# Switch-LIN-SIL-1.net
KiCad netlist of a schematic drawn in EAGLE
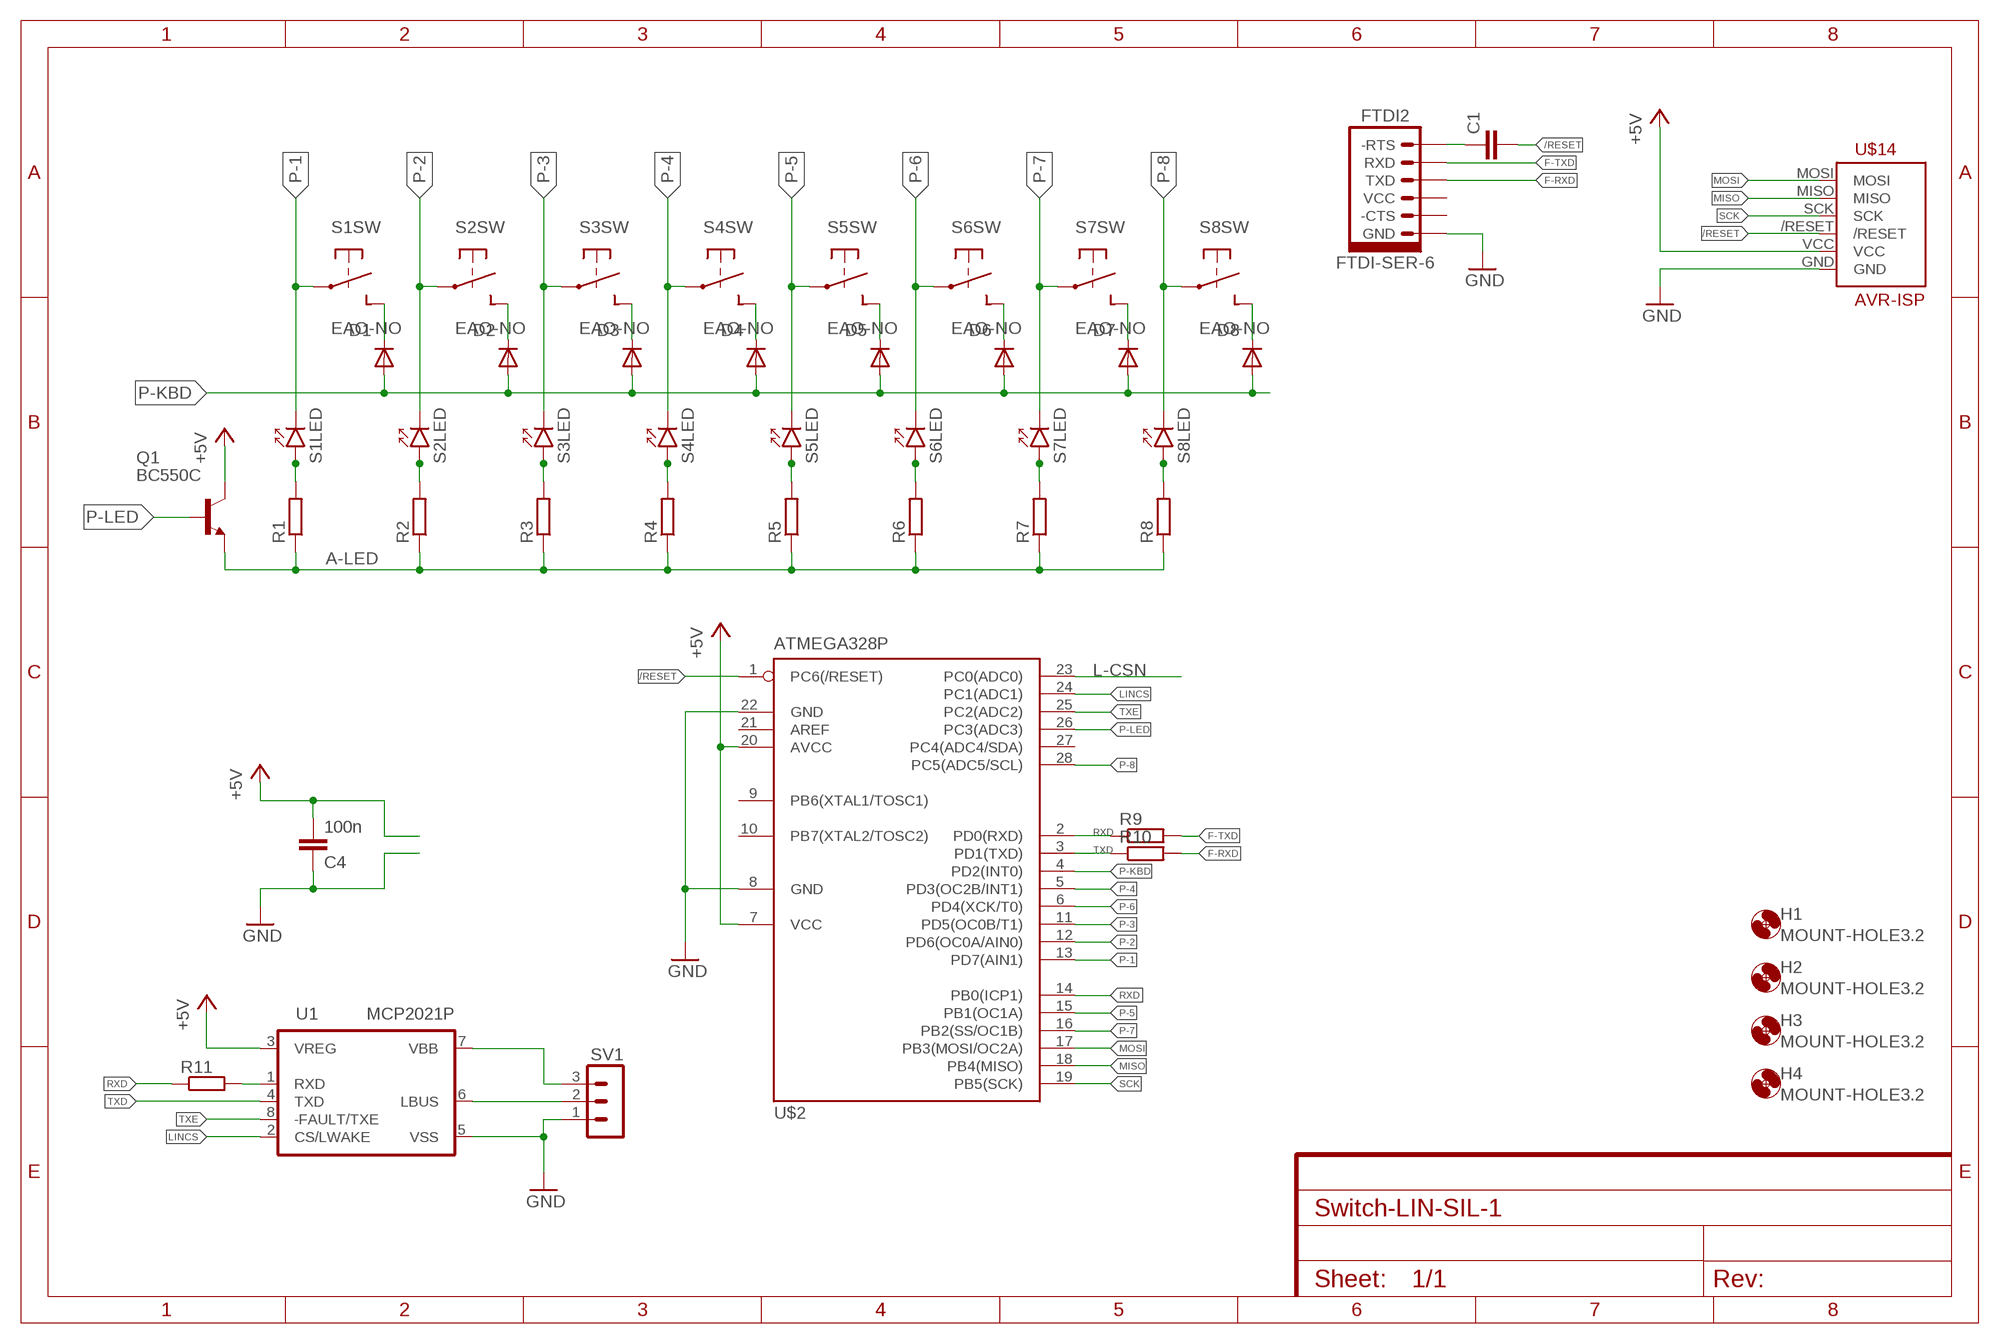
[diagram p0: schematic, sheet 1]

(export (version "E")
  (design (tool "Eeschema 10.0.6"))
  (components
    (comp (ref "C1")
      (value "C-EU025-025X050")
      (footprint "eagle-import:C025-025X050")
      (libsource (lib "eagle-import") (part "C-EU025-025X050"))
    )
    (comp (ref "C4")
      (value "100n")
      (footprint "eagle-import:C0805")
      (libsource (lib "eagle-import") (part "C-EUC0805"))
    )
    (comp (ref "D1")
      (value "1N4148")
      (footprint "eagle-import:DO35-7")
      (libsource (lib "eagle-import") (part "1N4148DO35-7"))
    )
    (comp (ref "D2")
      (value "1N4148")
      (footprint "eagle-import:DO35-7")
      (libsource (lib "eagle-import") (part "1N4148DO35-7"))
    )
    (comp (ref "D3")
      (value "1N4148")
      (footprint "eagle-import:DO35-7")
      (libsource (lib "eagle-import") (part "1N4148DO35-7"))
    )
    (comp (ref "D4")
      (value "1N4148")
      (footprint "eagle-import:DO35-7")
      (libsource (lib "eagle-import") (part "1N4148DO35-7"))
    )
    (comp (ref "D5")
      (value "1N4148")
      (footprint "eagle-import:DO35-7")
      (libsource (lib "eagle-import") (part "1N4148DO35-7"))
    )
    (comp (ref "D6")
      (value "1N4148")
      (footprint "eagle-import:DO35-7")
      (libsource (lib "eagle-import") (part "1N4148DO35-7"))
    )
    (comp (ref "D7")
      (value "1N4148")
      (footprint "eagle-import:DO35-7")
      (libsource (lib "eagle-import") (part "1N4148DO35-7"))
    )
    (comp (ref "D8")
      (value "1N4148")
      (footprint "eagle-import:DO35-7")
      (libsource (lib "eagle-import") (part "1N4148DO35-7"))
    )
    (comp (ref "FTDI2")
      (value "FTDI-SER-6")
      (footprint "eagle-import:FTDI-SER-6")
      (libsource (lib "eagle-import") (part "FTDI-SER-6"))
    )
    (comp (ref "H1")
      (value "MOUNT-HOLE3.2")
      (footprint "eagle-import:3,2")
      (libsource (lib "eagle-import") (part "MOUNT-HOLE3.2"))
    )
    (comp (ref "H2")
      (value "MOUNT-HOLE3.2")
      (footprint "eagle-import:3,2")
      (libsource (lib "eagle-import") (part "MOUNT-HOLE3.2"))
    )
    (comp (ref "H3")
      (value "MOUNT-HOLE3.2")
      (footprint "eagle-import:3,2")
      (libsource (lib "eagle-import") (part "MOUNT-HOLE3.2"))
    )
    (comp (ref "H4")
      (value "MOUNT-HOLE3.2")
      (footprint "eagle-import:3,2")
      (libsource (lib "eagle-import") (part "MOUNT-HOLE3.2"))
    )
    (comp (ref "Q1")
      (value "BC550C")
      (footprint "eagle-import:TO92-EBC")
      (libsource (lib "eagle-import") (part "BC550C"))
    )
    (comp (ref "R1")
      (value "R-EU_0207/7")
      (footprint "eagle-import:0207_7")
      (libsource (lib "eagle-import") (part "R-EU_0207/7"))
    )
    (comp (ref "R2")
      (value "R-EU_0207/7")
      (footprint "eagle-import:0207_7")
      (libsource (lib "eagle-import") (part "R-EU_0207/7"))
    )
    (comp (ref "R3")
      (value "R-EU_0207/7")
      (footprint "eagle-import:0207_7")
      (libsource (lib "eagle-import") (part "R-EU_0207/7"))
    )
    (comp (ref "R4")
      (value "R-EU_0207/7")
      (footprint "eagle-import:0207_7")
      (libsource (lib "eagle-import") (part "R-EU_0207/7"))
    )
    (comp (ref "R5")
      (value "R-EU_0207/7")
      (footprint "eagle-import:0207_7")
      (libsource (lib "eagle-import") (part "R-EU_0207/7"))
    )
    (comp (ref "R6")
      (value "R-EU_0207/7")
      (footprint "eagle-import:0207_7")
      (libsource (lib "eagle-import") (part "R-EU_0207/7"))
    )
    (comp (ref "R7")
      (value "R-EU_0207/7")
      (footprint "eagle-import:0207_7")
      (libsource (lib "eagle-import") (part "R-EU_0207/7"))
    )
    (comp (ref "R8")
      (value "R-EU_0207/7")
      (footprint "eagle-import:0207_7")
      (libsource (lib "eagle-import") (part "R-EU_0207/7"))
    )
    (comp (ref "R9")
      (value "R-EU_0207/7")
      (footprint "eagle-import:0207_7")
      (libsource (lib "eagle-import") (part "R-EU_0207/7"))
    )
    (comp (ref "R10")
      (value "R-EU_0207/7")
      (footprint "eagle-import:0207_7")
      (libsource (lib "eagle-import") (part "R-EU_0207/7"))
    )
    (comp (ref "R11")
      (value "R-EU_0207/7")
      (footprint "eagle-import:0207_7")
      (libsource (lib "eagle-import") (part "R-EU_0207/7"))
    )
    (comp (ref "S1")
      (value "EAO-NO")
      (footprint "eagle-import:MA04-1")
      (libsource (lib "eagle-import") (part "EAO-NO"))
    )
    (comp (ref "S2")
      (value "EAO-NO")
      (footprint "eagle-import:MA04-1")
      (libsource (lib "eagle-import") (part "EAO-NO"))
    )
    (comp (ref "S3")
      (value "EAO-NO")
      (footprint "eagle-import:MA04-1")
      (libsource (lib "eagle-import") (part "EAO-NO"))
    )
    (comp (ref "S4")
      (value "EAO-NO")
      (footprint "eagle-import:MA04-1")
      (libsource (lib "eagle-import") (part "EAO-NO"))
    )
    (comp (ref "S5")
      (value "EAO-NO")
      (footprint "eagle-import:MA04-1")
      (libsource (lib "eagle-import") (part "EAO-NO"))
    )
    (comp (ref "S6")
      (value "EAO-NO")
      (footprint "eagle-import:MA04-1")
      (libsource (lib "eagle-import") (part "EAO-NO"))
    )
    (comp (ref "S7")
      (value "EAO-NO")
      (footprint "eagle-import:MA04-1")
      (libsource (lib "eagle-import") (part "EAO-NO"))
    )
    (comp (ref "S8")
      (value "EAO-NO")
      (footprint "eagle-import:MA04-1")
      (libsource (lib "eagle-import") (part "EAO-NO"))
    )
    (comp (ref "SV1")
      (value "MA03-1")
      (footprint "eagle-import:MA03-1")
      (libsource (lib "eagle-import") (part "MA03-1"))
    )
    (comp (ref "U$2")
      (value "ATMEGA328P")
      (footprint "eagle-import:DIL28-3")
      (libsource (lib "eagle-import") (part "ATMEGA328P"))
    )
    (comp (ref "U$14")
      (value "AVR-ISP")
      (footprint "eagle-import:AVR-ISP-SIL")
      (libsource (lib "eagle-import") (part "AVR-ISP"))
    )
    (comp (ref "U1")
      (value "MCP2021P")
      (footprint "eagle-import:DIL8")
      (libsource (lib "eagle-import") (part "MCP2021P"))
    )
  )
  (nets
    (net (code "1") (name "+5V") (class "Default")
      (node (ref "C4") (pin "2") (pinfunction "2_2") (pintype "passive"))
      (node (ref "Q1") (pin "C") (pinfunction "C_C") (pintype "passive"))
      (node (ref "U$14") (pin "VCC") (pinfunction "VCC_VCC") (pintype "bidirectional"))
      (node (ref "U$2") (pin "20") (pinfunction "AVCC_20") (pintype "power_in"))
      (node (ref "U$2") (pin "7") (pinfunction "VCC_7") (pintype "power_in"))
      (node (ref "U1") (pin "3") (pinfunction "VREG_3") (pintype "power_in"))
    )
    (net (code "2") (name "/A-LED") (class "Default")
      (node (ref "Q1") (pin "E") (pinfunction "E_E") (pintype "passive"))
      (node (ref "R1") (pin "1") (pinfunction "1_1") (pintype "passive"))
      (node (ref "R2") (pin "1") (pinfunction "1_1") (pintype "passive"))
      (node (ref "R3") (pin "1") (pinfunction "1_1") (pintype "passive"))
      (node (ref "R4") (pin "1") (pinfunction "1_1") (pintype "passive"))
      (node (ref "R5") (pin "1") (pinfunction "1_1") (pintype "passive"))
      (node (ref "R6") (pin "1") (pinfunction "1_1") (pintype "passive"))
      (node (ref "R7") (pin "1") (pinfunction "1_1") (pintype "passive"))
      (node (ref "R8") (pin "1") (pinfunction "1_1") (pintype "passive"))
    )
    (net (code "3") (name "/L-CSN") (class "Default")
      (node (ref "U$2") (pin "23") (pinfunction "PC0(ADC0)_23") (pintype "bidirectional"))
    )
    (net (code "4") (name "F-RXD") (class "Default")
      (node (ref "FTDI2") (pin "TXD") (pinfunction "TXD_TXD") (pintype "passive"))
      (node (ref "R10") (pin "2") (pinfunction "2_2") (pintype "passive"))
    )
    (net (code "5") (name "F-TXD") (class "Default")
      (node (ref "FTDI2") (pin "RXD") (pinfunction "RXD_RXD") (pintype "passive"))
      (node (ref "R9") (pin "2") (pinfunction "2_2") (pintype "passive"))
    )
    (net (code "6") (name "GND") (class "Default")
      (node (ref "C4") (pin "1") (pinfunction "1_1") (pintype "passive"))
      (node (ref "FTDI2") (pin "GND") (pinfunction "GND_GND") (pintype "passive"))
      (node (ref "SV1") (pin "1") (pinfunction "1_1") (pintype "passive"))
      (node (ref "U$14") (pin "GND") (pinfunction "GND_GND") (pintype "bidirectional"))
      (node (ref "U$2") (pin "22") (pinfunction "GND_22") (pintype "power_in"))
      (node (ref "U$2") (pin "8") (pinfunction "GND_8") (pintype "power_in"))
      (node (ref "U1") (pin "5") (pinfunction "VSS_5") (pintype "power_in"))
    )
    (net (code "7") (name "LINCS") (class "Default")
      (node (ref "U$2") (pin "24") (pinfunction "PC1(ADC1)_24") (pintype "bidirectional"))
      (node (ref "U1") (pin "2") (pinfunction "CS/LWAKE_2") (pintype "input"))
    )
    (net (code "8") (name "MISO") (class "Default")
      (node (ref "U$14") (pin "MISO") (pinfunction "MISO_MISO") (pintype "bidirectional"))
      (node (ref "U$2") (pin "18") (pinfunction "PB4(MISO)_18") (pintype "bidirectional"))
    )
    (net (code "9") (name "MOSI") (class "Default")
      (node (ref "U$14") (pin "MOSI") (pinfunction "MOSI_MOSI") (pintype "bidirectional"))
      (node (ref "U$2") (pin "17") (pinfunction "PB3(MOSI/OC2A)_17") (pintype "bidirectional"))
    )
    (net (code "10") (name "Net-(C1-Pad1)") (class "Default")
      (node (ref "C1") (pin "1") (pinfunction "1_1") (pintype "passive"))
      (node (ref "FTDI2") (pin "-RTS") (pinfunction "-RTS_-RTS") (pintype "passive"))
    )
    (net (code "11") (name "Net-(S1A-A)") (class "Default")
      (node (ref "R1") (pin "2") (pinfunction "2_2") (pintype "passive"))
      (node (ref "S1") (pin "2") (pinfunction "A_2") (pintype "passive"))
    )
    (net (code "12") (name "Net-(S1B-NO2)") (class "Default")
      (node (ref "D1") (pin "C") (pinfunction "C_C") (pintype "passive"))
      (node (ref "S1") (pin "4") (pinfunction "NO2_4") (pintype "passive"))
    )
    (net (code "13") (name "Net-(S2A-A)") (class "Default")
      (node (ref "R2") (pin "2") (pinfunction "2_2") (pintype "passive"))
      (node (ref "S2") (pin "2") (pinfunction "A_2") (pintype "passive"))
    )
    (net (code "14") (name "Net-(S2B-NO2)") (class "Default")
      (node (ref "D2") (pin "C") (pinfunction "C_C") (pintype "passive"))
      (node (ref "S2") (pin "4") (pinfunction "NO2_4") (pintype "passive"))
    )
    (net (code "15") (name "Net-(S3A-A)") (class "Default")
      (node (ref "R3") (pin "2") (pinfunction "2_2") (pintype "passive"))
      (node (ref "S3") (pin "2") (pinfunction "A_2") (pintype "passive"))
    )
    (net (code "16") (name "Net-(S3B-NO2)") (class "Default")
      (node (ref "D3") (pin "C") (pinfunction "C_C") (pintype "passive"))
      (node (ref "S3") (pin "4") (pinfunction "NO2_4") (pintype "passive"))
    )
    (net (code "17") (name "Net-(S4A-A)") (class "Default")
      (node (ref "R4") (pin "2") (pinfunction "2_2") (pintype "passive"))
      (node (ref "S4") (pin "2") (pinfunction "A_2") (pintype "passive"))
    )
    (net (code "18") (name "Net-(S4B-NO2)") (class "Default")
      (node (ref "D4") (pin "C") (pinfunction "C_C") (pintype "passive"))
      (node (ref "S4") (pin "4") (pinfunction "NO2_4") (pintype "passive"))
    )
    (net (code "19") (name "Net-(S5A-A)") (class "Default")
      (node (ref "R5") (pin "2") (pinfunction "2_2") (pintype "passive"))
      (node (ref "S5") (pin "2") (pinfunction "A_2") (pintype "passive"))
    )
    (net (code "20") (name "Net-(S5B-NO2)") (class "Default")
      (node (ref "D5") (pin "C") (pinfunction "C_C") (pintype "passive"))
      (node (ref "S5") (pin "4") (pinfunction "NO2_4") (pintype "passive"))
    )
    (net (code "21") (name "Net-(S6A-A)") (class "Default")
      (node (ref "R6") (pin "2") (pinfunction "2_2") (pintype "passive"))
      (node (ref "S6") (pin "2") (pinfunction "A_2") (pintype "passive"))
    )
    (net (code "22") (name "Net-(S6B-NO2)") (class "Default")
      (node (ref "D6") (pin "C") (pinfunction "C_C") (pintype "passive"))
      (node (ref "S6") (pin "4") (pinfunction "NO2_4") (pintype "passive"))
    )
    (net (code "23") (name "Net-(S7A-A)") (class "Default")
      (node (ref "R7") (pin "2") (pinfunction "2_2") (pintype "passive"))
      (node (ref "S7") (pin "2") (pinfunction "A_2") (pintype "passive"))
    )
    (net (code "24") (name "Net-(S7B-NO2)") (class "Default")
      (node (ref "D7") (pin "C") (pinfunction "C_C") (pintype "passive"))
      (node (ref "S7") (pin "4") (pinfunction "NO2_4") (pintype "passive"))
    )
    (net (code "25") (name "Net-(S8A-A)") (class "Default")
      (node (ref "R8") (pin "2") (pinfunction "2_2") (pintype "passive"))
      (node (ref "S8") (pin "2") (pinfunction "A_2") (pintype "passive"))
    )
    (net (code "26") (name "Net-(S8B-NO2)") (class "Default")
      (node (ref "D8") (pin "C") (pinfunction "C_C") (pintype "passive"))
      (node (ref "S8") (pin "4") (pinfunction "NO2_4") (pintype "passive"))
    )
    (net (code "27") (name "Net-(U1-LBUS)") (class "Default")
      (node (ref "SV1") (pin "2") (pinfunction "2_2") (pintype "passive"))
      (node (ref "U1") (pin "6") (pinfunction "LBUS_6") (pintype "bidirectional"))
    )
    (net (code "28") (name "Net-(U1-RXD)") (class "Default")
      (node (ref "R11") (pin "2") (pinfunction "2_2") (pintype "passive"))
      (node (ref "U1") (pin "1") (pinfunction "RXD_1") (pintype "output"))
    )
    (net (code "29") (name "Net-(U1-VBB)") (class "Default")
      (node (ref "SV1") (pin "3") (pinfunction "3_3") (pintype "passive"))
      (node (ref "U1") (pin "7") (pinfunction "VBB_7") (pintype "power_in"))
    )
    (net (code "30") (name "P-1") (class "Default")
      (node (ref "S1") (pin "1") (pinfunction "C_1") (pintype "passive"))
      (node (ref "S1") (pin "3") (pinfunction "NO1_3") (pintype "passive"))
      (node (ref "U$2") (pin "13") (pinfunction "PD7(AIN1)_13") (pintype "bidirectional"))
    )
    (net (code "31") (name "P-2") (class "Default")
      (node (ref "S2") (pin "1") (pinfunction "C_1") (pintype "passive"))
      (node (ref "S2") (pin "3") (pinfunction "NO1_3") (pintype "passive"))
      (node (ref "U$2") (pin "12") (pinfunction "PD6(OC0A/AIN0)_12") (pintype "bidirectional"))
    )
    (net (code "32") (name "P-3") (class "Default")
      (node (ref "S3") (pin "1") (pinfunction "C_1") (pintype "passive"))
      (node (ref "S3") (pin "3") (pinfunction "NO1_3") (pintype "passive"))
      (node (ref "U$2") (pin "11") (pinfunction "PD5(OC0B/T1)_11") (pintype "bidirectional"))
    )
    (net (code "33") (name "P-4") (class "Default")
      (node (ref "S4") (pin "1") (pinfunction "C_1") (pintype "passive"))
      (node (ref "S4") (pin "3") (pinfunction "NO1_3") (pintype "passive"))
      (node (ref "U$2") (pin "5") (pinfunction "PD3(OC2B/INT1)_5") (pintype "bidirectional"))
    )
    (net (code "34") (name "P-5") (class "Default")
      (node (ref "S5") (pin "1") (pinfunction "C_1") (pintype "passive"))
      (node (ref "S5") (pin "3") (pinfunction "NO1_3") (pintype "passive"))
      (node (ref "U$2") (pin "15") (pinfunction "PB1(OC1A)_15") (pintype "bidirectional"))
    )
    (net (code "35") (name "P-6") (class "Default")
      (node (ref "S6") (pin "1") (pinfunction "C_1") (pintype "passive"))
      (node (ref "S6") (pin "3") (pinfunction "NO1_3") (pintype "passive"))
      (node (ref "U$2") (pin "6") (pinfunction "PD4(XCK/T0)_6") (pintype "bidirectional"))
    )
    (net (code "36") (name "P-7") (class "Default")
      (node (ref "S7") (pin "1") (pinfunction "C_1") (pintype "passive"))
      (node (ref "S7") (pin "3") (pinfunction "NO1_3") (pintype "passive"))
      (node (ref "U$2") (pin "16") (pinfunction "PB2(SS/OC1B)_16") (pintype "bidirectional"))
    )
    (net (code "37") (name "P-8") (class "Default")
      (node (ref "S8") (pin "1") (pinfunction "C_1") (pintype "passive"))
      (node (ref "S8") (pin "3") (pinfunction "NO1_3") (pintype "passive"))
      (node (ref "U$2") (pin "28") (pinfunction "PC5(ADC5/SCL)_28") (pintype "bidirectional"))
    )
    (net (code "38") (name "P-KBD") (class "Default")
      (node (ref "D1") (pin "A") (pinfunction "A_A") (pintype "passive"))
      (node (ref "D2") (pin "A") (pinfunction "A_A") (pintype "passive"))
      (node (ref "D3") (pin "A") (pinfunction "A_A") (pintype "passive"))
      (node (ref "D4") (pin "A") (pinfunction "A_A") (pintype "passive"))
      (node (ref "D5") (pin "A") (pinfunction "A_A") (pintype "passive"))
      (node (ref "D6") (pin "A") (pinfunction "A_A") (pintype "passive"))
      (node (ref "D7") (pin "A") (pinfunction "A_A") (pintype "passive"))
      (node (ref "D8") (pin "A") (pinfunction "A_A") (pintype "passive"))
      (node (ref "U$2") (pin "4") (pinfunction "PD2(INT0)_4") (pintype "bidirectional"))
    )
    (net (code "39") (name "P-LED") (class "Default")
      (node (ref "Q1") (pin "B") (pinfunction "B_B") (pintype "passive"))
      (node (ref "U$2") (pin "26") (pinfunction "PC3(ADC3)_26") (pintype "bidirectional"))
    )
    (net (code "40") (name "RXD") (class "Default")
      (node (ref "R11") (pin "1") (pinfunction "1_1") (pintype "passive"))
      (node (ref "R9") (pin "1") (pinfunction "1_1") (pintype "passive"))
      (node (ref "U$2") (pin "14") (pinfunction "PB0(ICP1)_14") (pintype "bidirectional"))
      (node (ref "U$2") (pin "2") (pinfunction "PD0(RXD)_2") (pintype "bidirectional"))
    )
    (net (code "41") (name "SCK") (class "Default")
      (node (ref "U$14") (pin "SCK") (pinfunction "SCK_SCK") (pintype "bidirectional"))
      (node (ref "U$2") (pin "19") (pinfunction "PB5(SCK)_19") (pintype "bidirectional"))
    )
    (net (code "42") (name "TXD") (class "Default")
      (node (ref "R10") (pin "1") (pinfunction "1_1") (pintype "passive"))
      (node (ref "U$2") (pin "3") (pinfunction "PD1(TXD)_3") (pintype "bidirectional"))
      (node (ref "U1") (pin "4") (pinfunction "TXD_4") (pintype "input"))
    )
    (net (code "43") (name "TXE") (class "Default")
      (node (ref "U$2") (pin "25") (pinfunction "PC2(ADC2)_25") (pintype "bidirectional"))
      (node (ref "U1") (pin "8") (pinfunction "-FAULT/TXE_8") (pintype "bidirectional"))
    )
    (net (code "44") (name "unconnected-(FTDI2-Pad-CTS)") (class "Default")
      (node (ref "FTDI2") (pin "-CTS") (pinfunction "-CTS_-CTS") (pintype "passive"))
    )
    (net (code "45") (name "unconnected-(FTDI2-PadVCC)") (class "Default")
      (node (ref "FTDI2") (pin "VCC") (pinfunction "VCC_VCC") (pintype "passive"))
    )
    (net (code "46") (name "unconnected-(U$2-AREF-Pad21)") (class "Default")
      (node (ref "U$2") (pin "21") (pinfunction "AREF_21") (pintype "passive"))
    )
    (net (code "47") (name "unconnected-(U$2-PB6(XTAL1{slash}TOSC1)-Pad9)") (class "Default")
      (node (ref "U$2") (pin "9") (pinfunction "PB6(XTAL1/TOSC1)_9") (pintype "bidirectional"))
    )
    (net (code "48") (name "unconnected-(U$2-PB7(XTAL2{slash}TOSC2)-Pad10)") (class "Default")
      (node (ref "U$2") (pin "10") (pinfunction "PB7(XTAL2/TOSC2)_10") (pintype "bidirectional"))
    )
    (net (code "49") (name "unconnected-(U$2-PC4(ADC4{slash}SDA)-Pad27)") (class "Default")
      (node (ref "U$2") (pin "27") (pinfunction "PC4(ADC4/SDA)_27") (pintype "bidirectional"))
    )
    (net (code "50") (name "{slash}RESET") (class "Default")
      (node (ref "C1") (pin "2") (pinfunction "2_2") (pintype "passive"))
      (node (ref "U$14") (pin "/RESET") (pinfunction "/RESET_/RESET") (pintype "bidirectional"))
      (node (ref "U$2") (pin "1") (pinfunction "PC6(/RESET)_1") (pintype "bidirectional"))
    )
  )
)
